# AutoPilotPanel_-_Part_2.net
KiCad netlist of a schematic drawn in EAGLE
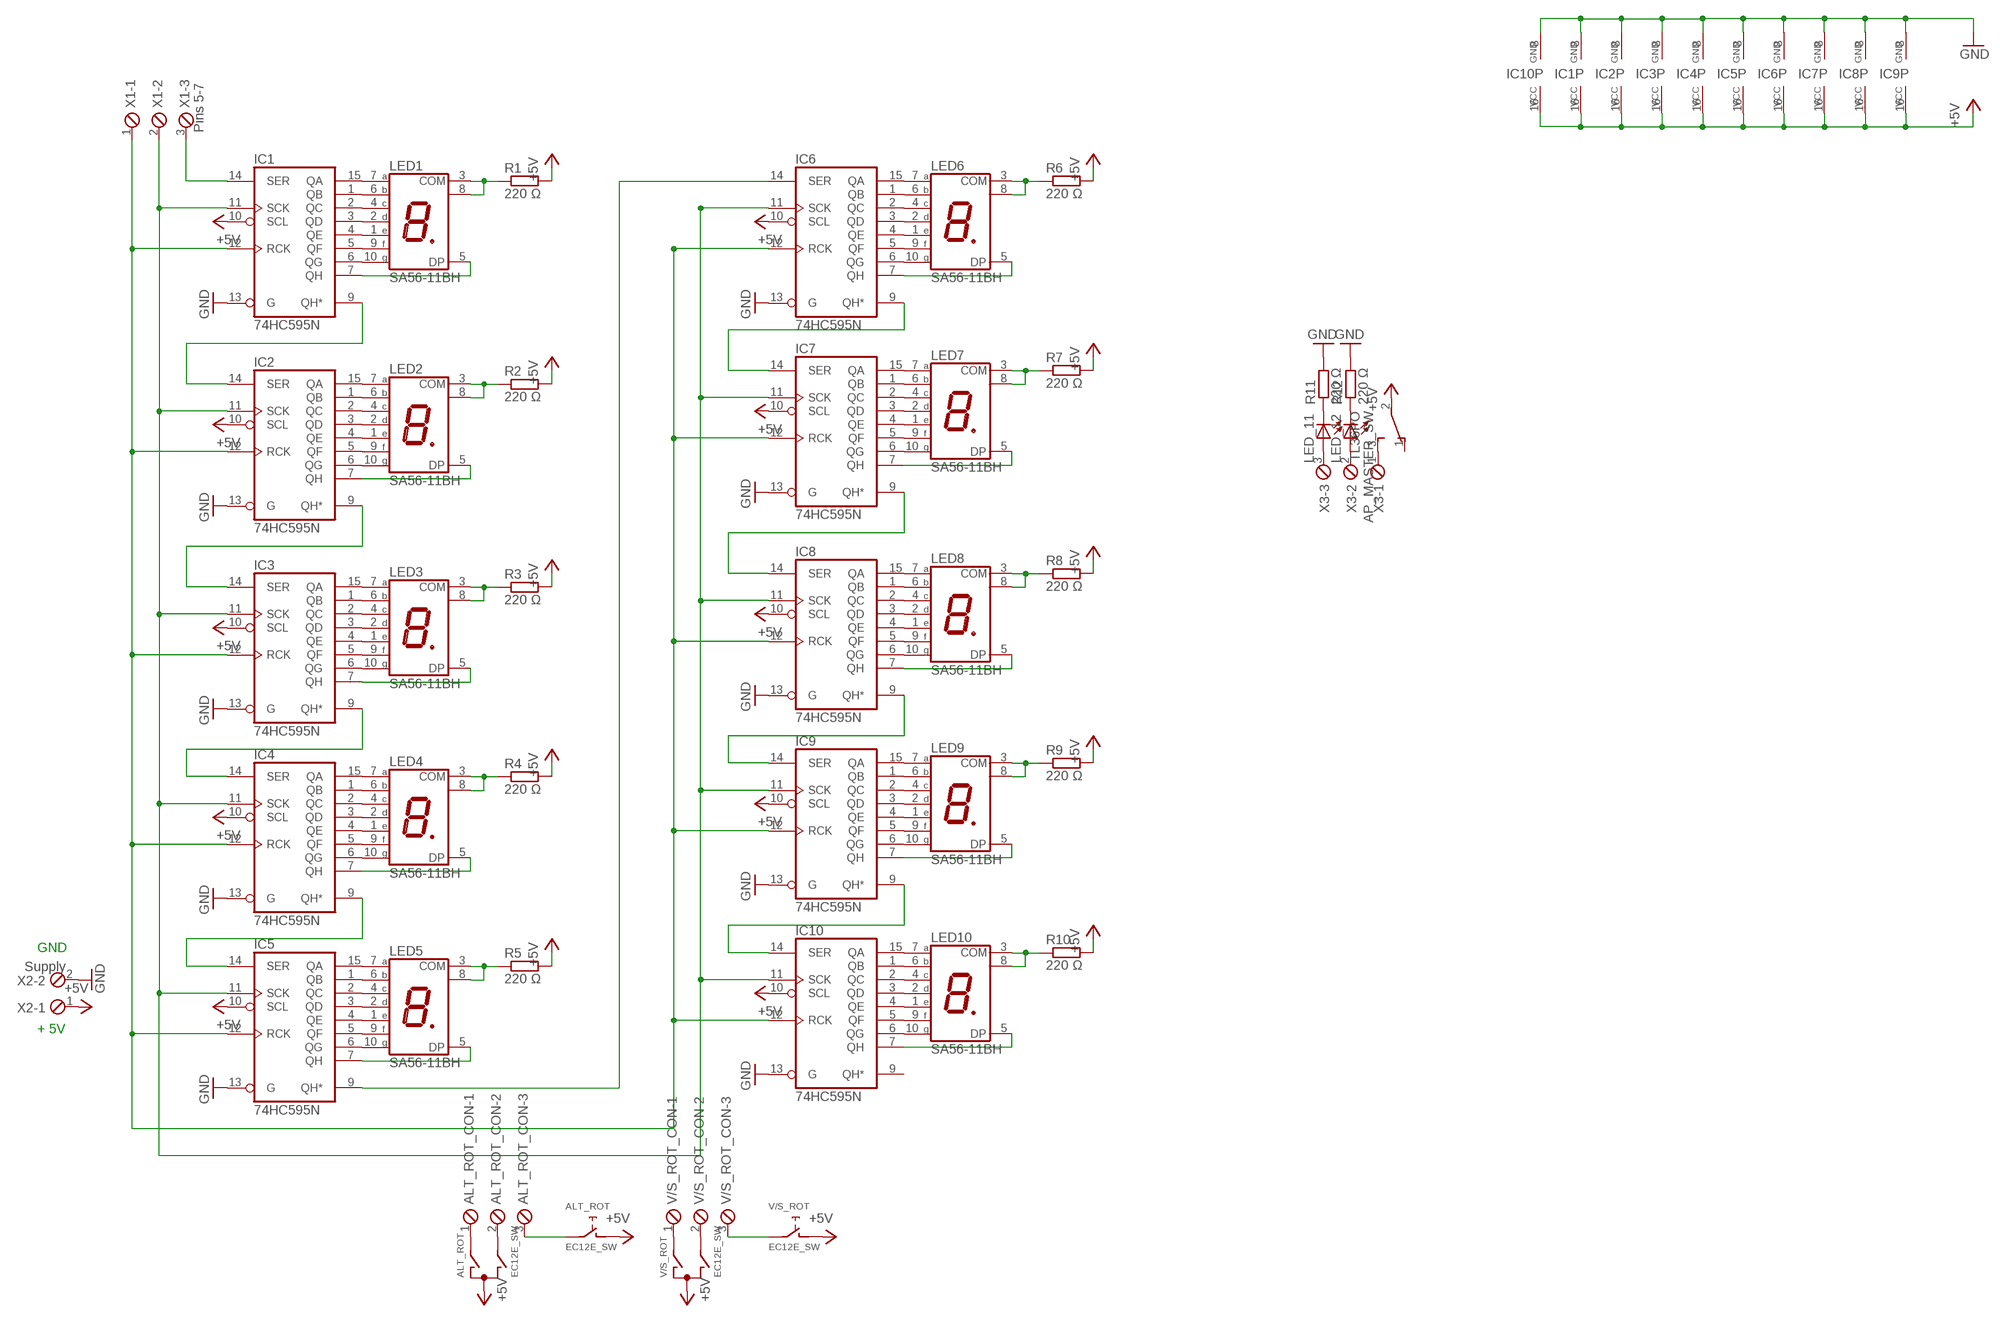
[diagram p0: schematic, sheet 1]

(export (version "E")
  (design (tool "Eeschema 10.0.6"))
  (components
    (comp (ref "ALT_ROT")
      (value "EC12E_SW")
      (footprint "eagle-import:ALPS_EC12E_SW")
      (fields (field (name "MPN") "EC12E2424407"))
      (libsource (lib "eagle-import") (part "EC12E_SW"))
    )
    (comp (ref "ALT_ROT_CON")
      (value "MPT3")
      (footprint "eagle-import:3POL254")
      (libsource (lib "eagle-import") (part "MPT3"))
    )
    (comp (ref "AP_MASTER_SW")
      (value "TL36PO")
      (footprint "eagle-import:TL3XPO")
      (libsource (lib "eagle-import") (part "TL36PO"))
    )
    (comp (ref "IC1")
      (value "74HC595N")
      (footprint "eagle-import:DIL16")
      (libsource (lib "eagle-import") (part "74595NHC"))
    )
    (comp (ref "IC2")
      (value "74HC595N")
      (footprint "eagle-import:DIL16")
      (libsource (lib "eagle-import") (part "74595NHC"))
    )
    (comp (ref "IC3")
      (value "74HC595N")
      (footprint "eagle-import:DIL16")
      (libsource (lib "eagle-import") (part "74595NHC"))
    )
    (comp (ref "IC4")
      (value "74HC595N")
      (footprint "eagle-import:DIL16")
      (libsource (lib "eagle-import") (part "74595NHC"))
    )
    (comp (ref "IC5")
      (value "74HC595N")
      (footprint "eagle-import:DIL16")
      (libsource (lib "eagle-import") (part "74595NHC"))
    )
    (comp (ref "IC6")
      (value "74HC595N")
      (footprint "eagle-import:DIL16")
      (libsource (lib "eagle-import") (part "74595NHC"))
    )
    (comp (ref "IC7")
      (value "74HC595N")
      (footprint "eagle-import:DIL16")
      (libsource (lib "eagle-import") (part "74595NHC"))
    )
    (comp (ref "IC8")
      (value "74HC595N")
      (footprint "eagle-import:DIL16")
      (libsource (lib "eagle-import") (part "74595NHC"))
    )
    (comp (ref "IC9")
      (value "74HC595N")
      (footprint "eagle-import:DIL16")
      (libsource (lib "eagle-import") (part "74595NHC"))
    )
    (comp (ref "IC10")
      (value "74HC595N")
      (footprint "eagle-import:DIL16")
      (libsource (lib "eagle-import") (part "74595NHC"))
    )
    (comp (ref "LED1")
      (value "SA56-11BH")
      (footprint "eagle-import:SA56-11")
      (libsource (lib "eagle-import") (part "7-SEG_SA56-11"))
    )
    (comp (ref "LED2")
      (value "SA56-11BH")
      (footprint "eagle-import:SA56-11")
      (libsource (lib "eagle-import") (part "7-SEG_SA56-11"))
    )
    (comp (ref "LED3")
      (value "SA56-11BH")
      (footprint "eagle-import:SA56-11")
      (libsource (lib "eagle-import") (part "7-SEG_SA56-11"))
    )
    (comp (ref "LED4")
      (value "SA56-11BH")
      (footprint "eagle-import:SA56-11")
      (libsource (lib "eagle-import") (part "7-SEG_SA56-11"))
    )
    (comp (ref "LED5")
      (value "SA56-11BH")
      (footprint "eagle-import:SA56-11")
      (libsource (lib "eagle-import") (part "7-SEG_SA56-11"))
    )
    (comp (ref "LED6")
      (value "SA56-11BH")
      (footprint "eagle-import:SA56-11")
      (libsource (lib "eagle-import") (part "7-SEG_SA56-11"))
    )
    (comp (ref "LED7")
      (value "SA56-11BH")
      (footprint "eagle-import:SA56-11")
      (libsource (lib "eagle-import") (part "7-SEG_SA56-11"))
    )
    (comp (ref "LED8")
      (value "SA56-11BH")
      (footprint "eagle-import:SA56-11")
      (libsource (lib "eagle-import") (part "7-SEG_SA56-11"))
    )
    (comp (ref "LED9")
      (value "SA56-11BH")
      (footprint "eagle-import:SA56-11")
      (libsource (lib "eagle-import") (part "7-SEG_SA56-11"))
    )
    (comp (ref "LED10")
      (value "SA56-11BH")
      (footprint "eagle-import:SA56-11")
      (libsource (lib "eagle-import") (part "7-SEG_SA56-11"))
    )
    (comp (ref "LED_11")
      (value "LED5MM")
      (footprint "eagle-import:LED5MM")
      (libsource (lib "eagle-import") (part "LED5MM"))
    )
    (comp (ref "LED_12")
      (value "LED5MM")
      (footprint "eagle-import:LED5MM")
      (libsource (lib "eagle-import") (part "LED5MM"))
    )
    (comp (ref "R1")
      (value "220 Ω")
      (footprint "eagle-import:0207_12")
      (libsource (lib "eagle-import") (part "R-EU_0207/12"))
    )
    (comp (ref "R2")
      (value "220 Ω")
      (footprint "eagle-import:0207_12")
      (libsource (lib "eagle-import") (part "R-EU_0207/12"))
    )
    (comp (ref "R3")
      (value "220 Ω")
      (footprint "eagle-import:0207_12")
      (libsource (lib "eagle-import") (part "R-EU_0207/12"))
    )
    (comp (ref "R4")
      (value "220 Ω")
      (footprint "eagle-import:0207_12")
      (libsource (lib "eagle-import") (part "R-EU_0207/12"))
    )
    (comp (ref "R5")
      (value "220 Ω")
      (footprint "eagle-import:0207_12")
      (libsource (lib "eagle-import") (part "R-EU_0207/12"))
    )
    (comp (ref "R6")
      (value "220 Ω")
      (footprint "eagle-import:0207_12")
      (libsource (lib "eagle-import") (part "R-EU_0207/12"))
    )
    (comp (ref "R7")
      (value "220 Ω")
      (footprint "eagle-import:0207_12")
      (libsource (lib "eagle-import") (part "R-EU_0207/12"))
    )
    (comp (ref "R8")
      (value "220 Ω")
      (footprint "eagle-import:0207_12")
      (libsource (lib "eagle-import") (part "R-EU_0207/12"))
    )
    (comp (ref "R9")
      (value "220 Ω")
      (footprint "eagle-import:0207_12")
      (libsource (lib "eagle-import") (part "R-EU_0207/12"))
    )
    (comp (ref "R10")
      (value "220 Ω")
      (footprint "eagle-import:0207_12")
      (libsource (lib "eagle-import") (part "R-EU_0207/12"))
    )
    (comp (ref "R11")
      (value "220 Ω")
      (footprint "eagle-import:0207_12")
      (libsource (lib "eagle-import") (part "R-EU_0207/12"))
    )
    (comp (ref "R12")
      (value "220 Ω")
      (footprint "eagle-import:0207_12")
      (libsource (lib "eagle-import") (part "R-EU_0207/12"))
    )
    (comp (ref "V/S_ROT")
      (value "EC12E_SW")
      (footprint "eagle-import:ALPS_EC12E_SW")
      (fields (field (name "MPN") "EC12E2424407"))
      (libsource (lib "eagle-import") (part "EC12E_SW"))
    )
    (comp (ref "V/S_ROT_CON")
      (value "MPT3")
      (footprint "eagle-import:3POL254")
      (libsource (lib "eagle-import") (part "MPT3"))
    )
    (comp (ref "X1")
      (value "Pins 5-7")
      (footprint "eagle-import:3POL254")
      (libsource (lib "eagle-import") (part "MPT3"))
    )
    (comp (ref "X2")
      (value "Supply")
      (footprint "eagle-import:2POL254")
      (libsource (lib "eagle-import") (part "MPT2"))
    )
    (comp (ref "X3")
      (value "MPT3")
      (footprint "eagle-import:3POL254")
      (libsource (lib "eagle-import") (part "MPT3"))
    )
  )
  (nets
    (net (code "1") (name "+5V") (class "Default")
      (node (ref "ALT_ROT") (pin "C") (pinfunction "C_C") (pintype "passive"))
      (node (ref "ALT_ROT") (pin "D") (pinfunction "1_D") (pintype "passive"))
      (node (ref "AP_MASTER_SW") (pin "2") (pinfunction "P_2") (pintype "passive"))
      (node (ref "IC1") (pin "10") (pinfunction "SCL_10") (pintype "input"))
      (node (ref "IC1") (pin "16") (pinfunction "VCC_16") (pintype "power_in"))
      (node (ref "IC10") (pin "10") (pinfunction "SCL_10") (pintype "input"))
      (node (ref "IC10") (pin "16") (pinfunction "VCC_16") (pintype "power_in"))
      (node (ref "IC2") (pin "10") (pinfunction "SCL_10") (pintype "input"))
      (node (ref "IC2") (pin "16") (pinfunction "VCC_16") (pintype "power_in"))
      (node (ref "IC3") (pin "10") (pinfunction "SCL_10") (pintype "input"))
      (node (ref "IC3") (pin "16") (pinfunction "VCC_16") (pintype "power_in"))
      (node (ref "IC4") (pin "10") (pinfunction "SCL_10") (pintype "input"))
      (node (ref "IC4") (pin "16") (pinfunction "VCC_16") (pintype "power_in"))
      (node (ref "IC5") (pin "10") (pinfunction "SCL_10") (pintype "input"))
      (node (ref "IC5") (pin "16") (pinfunction "VCC_16") (pintype "power_in"))
      (node (ref "IC6") (pin "10") (pinfunction "SCL_10") (pintype "input"))
      (node (ref "IC6") (pin "16") (pinfunction "VCC_16") (pintype "power_in"))
      (node (ref "IC7") (pin "10") (pinfunction "SCL_10") (pintype "input"))
      (node (ref "IC7") (pin "16") (pinfunction "VCC_16") (pintype "power_in"))
      (node (ref "IC8") (pin "10") (pinfunction "SCL_10") (pintype "input"))
      (node (ref "IC8") (pin "16") (pinfunction "VCC_16") (pintype "power_in"))
      (node (ref "IC9") (pin "10") (pinfunction "SCL_10") (pintype "input"))
      (node (ref "IC9") (pin "16") (pinfunction "VCC_16") (pintype "power_in"))
      (node (ref "R1") (pin "2") (pinfunction "2_2") (pintype "passive"))
      (node (ref "R10") (pin "2") (pinfunction "2_2") (pintype "passive"))
      (node (ref "R2") (pin "2") (pinfunction "2_2") (pintype "passive"))
      (node (ref "R3") (pin "2") (pinfunction "2_2") (pintype "passive"))
      (node (ref "R4") (pin "2") (pinfunction "2_2") (pintype "passive"))
      (node (ref "R5") (pin "2") (pinfunction "2_2") (pintype "passive"))
      (node (ref "R6") (pin "2") (pinfunction "2_2") (pintype "passive"))
      (node (ref "R7") (pin "2") (pinfunction "2_2") (pintype "passive"))
      (node (ref "R8") (pin "2") (pinfunction "2_2") (pintype "passive"))
      (node (ref "R9") (pin "2") (pinfunction "2_2") (pintype "passive"))
      (node (ref "V/S_ROT") (pin "C") (pinfunction "C_C") (pintype "passive"))
      (node (ref "V/S_ROT") (pin "D") (pinfunction "1_D") (pintype "passive"))
      (node (ref "X2") (pin "1") (pinfunction "1_1") (pintype "passive"))
    )
    (net (code "2") (name "GND") (class "Default")
      (node (ref "IC1") (pin "13") (pinfunction "G_13") (pintype "input"))
      (node (ref "IC1") (pin "8") (pinfunction "GND_8") (pintype "power_in"))
      (node (ref "IC10") (pin "13") (pinfunction "G_13") (pintype "input"))
      (node (ref "IC10") (pin "8") (pinfunction "GND_8") (pintype "power_in"))
      (node (ref "IC2") (pin "13") (pinfunction "G_13") (pintype "input"))
      (node (ref "IC2") (pin "8") (pinfunction "GND_8") (pintype "power_in"))
      (node (ref "IC3") (pin "13") (pinfunction "G_13") (pintype "input"))
      (node (ref "IC3") (pin "8") (pinfunction "GND_8") (pintype "power_in"))
      (node (ref "IC4") (pin "13") (pinfunction "G_13") (pintype "input"))
      (node (ref "IC4") (pin "8") (pinfunction "GND_8") (pintype "power_in"))
      (node (ref "IC5") (pin "13") (pinfunction "G_13") (pintype "input"))
      (node (ref "IC5") (pin "8") (pinfunction "GND_8") (pintype "power_in"))
      (node (ref "IC6") (pin "13") (pinfunction "G_13") (pintype "input"))
      (node (ref "IC6") (pin "8") (pinfunction "GND_8") (pintype "power_in"))
      (node (ref "IC7") (pin "13") (pinfunction "G_13") (pintype "input"))
      (node (ref "IC7") (pin "8") (pinfunction "GND_8") (pintype "power_in"))
      (node (ref "IC8") (pin "13") (pinfunction "G_13") (pintype "input"))
      (node (ref "IC8") (pin "8") (pinfunction "GND_8") (pintype "power_in"))
      (node (ref "IC9") (pin "13") (pinfunction "G_13") (pintype "input"))
      (node (ref "IC9") (pin "8") (pinfunction "GND_8") (pintype "power_in"))
      (node (ref "R11") (pin "2") (pinfunction "2_2") (pintype "passive"))
      (node (ref "R12") (pin "2") (pinfunction "2_2") (pintype "passive"))
      (node (ref "X2") (pin "2") (pinfunction "1_2") (pintype "passive"))
    )
    (net (code "3") (name "Net-(ALT_ROT-PadA)") (class "Default")
      (node (ref "ALT_ROT") (pin "A") (pinfunction "A_A") (pintype "passive"))
      (node (ref "ALT_ROT_CON") (pin "1") (pinfunction "1_1") (pintype "passive"))
    )
    (net (code "4") (name "Net-(ALT_ROTB-2)") (class "Default")
      (node (ref "ALT_ROT") (pin "E") (pinfunction "2_E") (pintype "passive"))
      (node (ref "ALT_ROT_CON") (pin "3") (pinfunction "1_3") (pintype "passive"))
    )
    (net (code "5") (name "Net-(ALT_ROT_CONB-1)") (class "Default")
      (node (ref "ALT_ROT") (pin "B") (pinfunction "B_B") (pintype "passive"))
      (node (ref "ALT_ROT_CON") (pin "2") (pinfunction "1_2") (pintype "passive"))
    )
    (net (code "6") (name "Net-(AP_MASTER_SW-S)") (class "Default")
      (node (ref "AP_MASTER_SW") (pin "3") (pinfunction "S_3") (pintype "passive"))
      (node (ref "X3") (pin "1") (pinfunction "1_1") (pintype "passive"))
    )
    (net (code "7") (name "Net-(IC1A-QA)") (class "Default")
      (node (ref "IC1") (pin "15") (pinfunction "QA_15") (pintype "tri_state"))
      (node (ref "LED1") (pin "7") (pinfunction "A_7") (pintype "passive"))
    )
    (net (code "8") (name "Net-(IC1A-QB)") (class "Default")
      (node (ref "IC1") (pin "1") (pinfunction "QB_1") (pintype "tri_state"))
      (node (ref "LED1") (pin "6") (pinfunction "B_6") (pintype "passive"))
    )
    (net (code "9") (name "Net-(IC1A-QC)") (class "Default")
      (node (ref "IC1") (pin "2") (pinfunction "QC_2") (pintype "tri_state"))
      (node (ref "LED1") (pin "4") (pinfunction "C_4") (pintype "passive"))
    )
    (net (code "10") (name "Net-(IC1A-QD)") (class "Default")
      (node (ref "IC1") (pin "3") (pinfunction "QD_3") (pintype "tri_state"))
      (node (ref "LED1") (pin "2") (pinfunction "D_2") (pintype "passive"))
    )
    (net (code "11") (name "Net-(IC1A-QE)") (class "Default")
      (node (ref "IC1") (pin "4") (pinfunction "QE_4") (pintype "tri_state"))
      (node (ref "LED1") (pin "1") (pinfunction "E_1") (pintype "passive"))
    )
    (net (code "12") (name "Net-(IC1A-QF)") (class "Default")
      (node (ref "IC1") (pin "5") (pinfunction "QF_5") (pintype "tri_state"))
      (node (ref "LED1") (pin "9") (pinfunction "F_9") (pintype "passive"))
    )
    (net (code "13") (name "Net-(IC1A-QG)") (class "Default")
      (node (ref "IC1") (pin "6") (pinfunction "QG_6") (pintype "tri_state"))
      (node (ref "LED1") (pin "10") (pinfunction "G_10") (pintype "passive"))
    )
    (net (code "14") (name "Net-(IC1A-QH)") (class "Default")
      (node (ref "IC1") (pin "7") (pinfunction "QH_7") (pintype "tri_state"))
      (node (ref "LED1") (pin "5") (pinfunction "DP_5") (pintype "passive"))
    )
    (net (code "15") (name "Net-(IC1A-QH*)") (class "Default")
      (node (ref "IC1") (pin "9") (pinfunction "QH*_9") (pintype "tri_state"))
      (node (ref "IC2") (pin "14") (pinfunction "SER_14") (pintype "input"))
    )
    (net (code "16") (name "Net-(IC1A-SER)") (class "Default")
      (node (ref "IC1") (pin "14") (pinfunction "SER_14") (pintype "input"))
      (node (ref "X1") (pin "3") (pinfunction "1_3") (pintype "passive"))
    )
    (net (code "17") (name "Net-(IC2A-QA)") (class "Default")
      (node (ref "IC2") (pin "15") (pinfunction "QA_15") (pintype "tri_state"))
      (node (ref "LED2") (pin "7") (pinfunction "A_7") (pintype "passive"))
    )
    (net (code "18") (name "Net-(IC2A-QB)") (class "Default")
      (node (ref "IC2") (pin "1") (pinfunction "QB_1") (pintype "tri_state"))
      (node (ref "LED2") (pin "6") (pinfunction "B_6") (pintype "passive"))
    )
    (net (code "19") (name "Net-(IC2A-QC)") (class "Default")
      (node (ref "IC2") (pin "2") (pinfunction "QC_2") (pintype "tri_state"))
      (node (ref "LED2") (pin "4") (pinfunction "C_4") (pintype "passive"))
    )
    (net (code "20") (name "Net-(IC2A-QD)") (class "Default")
      (node (ref "IC2") (pin "3") (pinfunction "QD_3") (pintype "tri_state"))
      (node (ref "LED2") (pin "2") (pinfunction "D_2") (pintype "passive"))
    )
    (net (code "21") (name "Net-(IC2A-QE)") (class "Default")
      (node (ref "IC2") (pin "4") (pinfunction "QE_4") (pintype "tri_state"))
      (node (ref "LED2") (pin "1") (pinfunction "E_1") (pintype "passive"))
    )
    (net (code "22") (name "Net-(IC2A-QF)") (class "Default")
      (node (ref "IC2") (pin "5") (pinfunction "QF_5") (pintype "tri_state"))
      (node (ref "LED2") (pin "9") (pinfunction "F_9") (pintype "passive"))
    )
    (net (code "23") (name "Net-(IC2A-QG)") (class "Default")
      (node (ref "IC2") (pin "6") (pinfunction "QG_6") (pintype "tri_state"))
      (node (ref "LED2") (pin "10") (pinfunction "G_10") (pintype "passive"))
    )
    (net (code "24") (name "Net-(IC2A-QH)") (class "Default")
      (node (ref "IC2") (pin "7") (pinfunction "QH_7") (pintype "tri_state"))
      (node (ref "LED2") (pin "5") (pinfunction "DP_5") (pintype "passive"))
    )
    (net (code "25") (name "Net-(IC2A-QH*)") (class "Default")
      (node (ref "IC2") (pin "9") (pinfunction "QH*_9") (pintype "tri_state"))
      (node (ref "IC3") (pin "14") (pinfunction "SER_14") (pintype "input"))
    )
    (net (code "26") (name "Net-(IC3A-QA)") (class "Default")
      (node (ref "IC3") (pin "15") (pinfunction "QA_15") (pintype "tri_state"))
      (node (ref "LED3") (pin "7") (pinfunction "A_7") (pintype "passive"))
    )
    (net (code "27") (name "Net-(IC3A-QB)") (class "Default")
      (node (ref "IC3") (pin "1") (pinfunction "QB_1") (pintype "tri_state"))
      (node (ref "LED3") (pin "6") (pinfunction "B_6") (pintype "passive"))
    )
    (net (code "28") (name "Net-(IC3A-QC)") (class "Default")
      (node (ref "IC3") (pin "2") (pinfunction "QC_2") (pintype "tri_state"))
      (node (ref "LED3") (pin "4") (pinfunction "C_4") (pintype "passive"))
    )
    (net (code "29") (name "Net-(IC3A-QD)") (class "Default")
      (node (ref "IC3") (pin "3") (pinfunction "QD_3") (pintype "tri_state"))
      (node (ref "LED3") (pin "2") (pinfunction "D_2") (pintype "passive"))
    )
    (net (code "30") (name "Net-(IC3A-QE)") (class "Default")
      (node (ref "IC3") (pin "4") (pinfunction "QE_4") (pintype "tri_state"))
      (node (ref "LED3") (pin "1") (pinfunction "E_1") (pintype "passive"))
    )
    (net (code "31") (name "Net-(IC3A-QF)") (class "Default")
      (node (ref "IC3") (pin "5") (pinfunction "QF_5") (pintype "tri_state"))
      (node (ref "LED3") (pin "9") (pinfunction "F_9") (pintype "passive"))
    )
    (net (code "32") (name "Net-(IC3A-QG)") (class "Default")
      (node (ref "IC3") (pin "6") (pinfunction "QG_6") (pintype "tri_state"))
      (node (ref "LED3") (pin "10") (pinfunction "G_10") (pintype "passive"))
    )
    (net (code "33") (name "Net-(IC3A-QH)") (class "Default")
      (node (ref "IC3") (pin "7") (pinfunction "QH_7") (pintype "tri_state"))
      (node (ref "LED3") (pin "5") (pinfunction "DP_5") (pintype "passive"))
    )
    (net (code "34") (name "Net-(IC3A-QH*)") (class "Default")
      (node (ref "IC3") (pin "9") (pinfunction "QH*_9") (pintype "tri_state"))
      (node (ref "IC4") (pin "14") (pinfunction "SER_14") (pintype "input"))
    )
    (net (code "35") (name "Net-(IC4A-QA)") (class "Default")
      (node (ref "IC4") (pin "15") (pinfunction "QA_15") (pintype "tri_state"))
      (node (ref "LED4") (pin "7") (pinfunction "A_7") (pintype "passive"))
    )
    (net (code "36") (name "Net-(IC4A-QB)") (class "Default")
      (node (ref "IC4") (pin "1") (pinfunction "QB_1") (pintype "tri_state"))
      (node (ref "LED4") (pin "6") (pinfunction "B_6") (pintype "passive"))
    )
    (net (code "37") (name "Net-(IC4A-QC)") (class "Default")
      (node (ref "IC4") (pin "2") (pinfunction "QC_2") (pintype "tri_state"))
      (node (ref "LED4") (pin "4") (pinfunction "C_4") (pintype "passive"))
    )
    (net (code "38") (name "Net-(IC4A-QD)") (class "Default")
      (node (ref "IC4") (pin "3") (pinfunction "QD_3") (pintype "tri_state"))
      (node (ref "LED4") (pin "2") (pinfunction "D_2") (pintype "passive"))
    )
    (net (code "39") (name "Net-(IC4A-QE)") (class "Default")
      (node (ref "IC4") (pin "4") (pinfunction "QE_4") (pintype "tri_state"))
      (node (ref "LED4") (pin "1") (pinfunction "E_1") (pintype "passive"))
    )
    (net (code "40") (name "Net-(IC4A-QF)") (class "Default")
      (node (ref "IC4") (pin "5") (pinfunction "QF_5") (pintype "tri_state"))
      (node (ref "LED4") (pin "9") (pinfunction "F_9") (pintype "passive"))
    )
    (net (code "41") (name "Net-(IC4A-QG)") (class "Default")
      (node (ref "IC4") (pin "6") (pinfunction "QG_6") (pintype "tri_state"))
      (node (ref "LED4") (pin "10") (pinfunction "G_10") (pintype "passive"))
    )
    (net (code "42") (name "Net-(IC4A-QH)") (class "Default")
      (node (ref "IC4") (pin "7") (pinfunction "QH_7") (pintype "tri_state"))
      (node (ref "LED4") (pin "5") (pinfunction "DP_5") (pintype "passive"))
    )
    (net (code "43") (name "Net-(IC4A-QH*)") (class "Default")
      (node (ref "IC4") (pin "9") (pinfunction "QH*_9") (pintype "tri_state"))
      (node (ref "IC5") (pin "14") (pinfunction "SER_14") (pintype "input"))
    )
    (net (code "44") (name "Net-(IC5A-QA)") (class "Default")
      (node (ref "IC5") (pin "15") (pinfunction "QA_15") (pintype "tri_state"))
      (node (ref "LED5") (pin "7") (pinfunction "A_7") (pintype "passive"))
    )
    (net (code "45") (name "Net-(IC5A-QB)") (class "Default")
      (node (ref "IC5") (pin "1") (pinfunction "QB_1") (pintype "tri_state"))
      (node (ref "LED5") (pin "6") (pinfunction "B_6") (pintype "passive"))
    )
    (net (code "46") (name "Net-(IC5A-QC)") (class "Default")
      (node (ref "IC5") (pin "2") (pinfunction "QC_2") (pintype "tri_state"))
      (node (ref "LED5") (pin "4") (pinfunction "C_4") (pintype "passive"))
    )
    (net (code "47") (name "Net-(IC5A-QD)") (class "Default")
      (node (ref "IC5") (pin "3") (pinfunction "QD_3") (pintype "tri_state"))
      (node (ref "LED5") (pin "2") (pinfunction "D_2") (pintype "passive"))
    )
    (net (code "48") (name "Net-(IC5A-QE)") (class "Default")
      (node (ref "IC5") (pin "4") (pinfunction "QE_4") (pintype "tri_state"))
      (node (ref "LED5") (pin "1") (pinfunction "E_1") (pintype "passive"))
    )
    (net (code "49") (name "Net-(IC5A-QF)") (class "Default")
      (node (ref "IC5") (pin "5") (pinfunction "QF_5") (pintype "tri_state"))
      (node (ref "LED5") (pin "9") (pinfunction "F_9") (pintype "passive"))
    )
    (net (code "50") (name "Net-(IC5A-QG)") (class "Default")
      (node (ref "IC5") (pin "6") (pinfunction "QG_6") (pintype "tri_state"))
      (node (ref "LED5") (pin "10") (pinfunction "G_10") (pintype "passive"))
    )
    (net (code "51") (name "Net-(IC5A-QH)") (class "Default")
      (node (ref "IC5") (pin "7") (pinfunction "QH_7") (pintype "tri_state"))
      (node (ref "LED5") (pin "5") (pinfunction "DP_5") (pintype "passive"))
    )
    (net (code "52") (name "Net-(IC5A-QH*)") (class "Default")
      (node (ref "IC5") (pin "9") (pinfunction "QH*_9") (pintype "tri_state"))
      (node (ref "IC6") (pin "14") (pinfunction "SER_14") (pintype "input"))
    )
    (net (code "53") (name "Net-(IC6A-QA)") (class "Default")
      (node (ref "IC6") (pin "15") (pinfunction "QA_15") (pintype "tri_state"))
      (node (ref "LED6") (pin "7") (pinfunction "A_7") (pintype "passive"))
    )
    (net (code "54") (name "Net-(IC6A-QB)") (class "Default")
      (node (ref "IC6") (pin "1") (pinfunction "QB_1") (pintype "tri_state"))
      (node (ref "LED6") (pin "6") (pinfunction "B_6") (pintype "passive"))
    )
    (net (code "55") (name "Net-(IC6A-QC)") (class "Default")
      (node (ref "IC6") (pin "2") (pinfunction "QC_2") (pintype "tri_state"))
      (node (ref "LED6") (pin "4") (pinfunction "C_4") (pintype "passive"))
    )
    (net (code "56") (name "Net-(IC6A-QD)") (class "Default")
      (node (ref "IC6") (pin "3") (pinfunction "QD_3") (pintype "tri_state"))
      (node (ref "LED6") (pin "2") (pinfunction "D_2") (pintype "passive"))
    )
    (net (code "57") (name "Net-(IC6A-QE)") (class "Default")
      (node (ref "IC6") (pin "4") (pinfunction "QE_4") (pintype "tri_state"))
      (node (ref "LED6") (pin "1") (pinfunction "E_1") (pintype "passive"))
    )
    (net (code "58") (name "Net-(IC6A-QF)") (class "Default")
      (node (ref "IC6") (pin "5") (pinfunction "QF_5") (pintype "tri_state"))
      (node (ref "LED6") (pin "9") (pinfunction "F_9") (pintype "passive"))
    )
    (net (code "59") (name "Net-(IC6A-QG)") (class "Default")
      (node (ref "IC6") (pin "6") (pinfunction "QG_6") (pintype "tri_state"))
      (node (ref "LED6") (pin "10") (pinfunction "G_10") (pintype "passive"))
    )
    (net (code "60") (name "Net-(IC6A-QH)") (class "Default")
      (node (ref "IC6") (pin "7") (pinfunction "QH_7") (pintype "tri_state"))
      (node (ref "LED6") (pin "5") (pinfunction "DP_5") (pintype "passive"))
    )
    (net (code "61") (name "Net-(IC6A-QH*)") (class "Default")
      (node (ref "IC6") (pin "9") (pinfunction "QH*_9") (pintype "tri_state"))
      (node (ref "IC7") (pin "14") (pinfunction "SER_14") (pintype "input"))
    )
    (net (code "62") (name "Net-(IC7A-QA)") (class "Default")
      (node (ref "IC7") (pin "15") (pinfunction "QA_15") (pintype "tri_state"))
      (node (ref "LED7") (pin "7") (pinfunction "A_7") (pintype "passive"))
    )
    (net (code "63") (name "Net-(IC7A-QB)") (class "Default")
      (node (ref "IC7") (pin "1") (pinfunction "QB_1") (pintype "tri_state"))
      (node (ref "LED7") (pin "6") (pinfunction "B_6") (pintype "passive"))
    )
    (net (code "64") (name "Net-(IC7A-QC)") (class "Default")
      (node (ref "IC7") (pin "2") (pinfunction "QC_2") (pintype "tri_state"))
      (node (ref "LED7") (pin "4") (pinfunction "C_4") (pintype "passive"))
    )
    (net (code "65") (name "Net-(IC7A-QD)") (class "Default")
      (node (ref "IC7") (pin "3") (pinfunction "QD_3") (pintype "tri_state"))
      (node (ref "LED7") (pin "2") (pinfunction "D_2") (pintype "passive"))
    )
    (net (code "66") (name "Net-(IC7A-QE)") (class "Default")
      (node (ref "IC7") (pin "4") (pinfunction "QE_4") (pintype "tri_state"))
      (node (ref "LED7") (pin "1") (pinfunction "E_1") (pintype "passive"))
    )
    (net (code "67") (name "Net-(IC7A-QF)") (class "Default")
      (node (ref "IC7") (pin "5") (pinfunction "QF_5") (pintype "tri_state"))
      (node (ref "LED7") (pin "9") (pinfunction "F_9") (pintype "passive"))
    )
    (net (code "68") (name "Net-(IC7A-QG)") (class "Default")
      (node (ref "IC7") (pin "6") (pinfunction "QG_6") (pintype "tri_state"))
      (node (ref "LED7") (pin "10") (pinfunction "G_10") (pintype "passive"))
    )
    (net (code "69") (name "Net-(IC7A-QH)") (class "Default")
      (node (ref "IC7") (pin "7") (pinfunction "QH_7") (pintype "tri_state"))
      (node (ref "LED7") (pin "5") (pinfunction "DP_5") (pintype "passive"))
    )
    (net (code "70") (name "Net-(IC7A-QH*)") (class "Default")
      (node (ref "IC7") (pin "9") (pinfunction "QH*_9") (pintype "tri_state"))
      (node (ref "IC8") (pin "14") (pinfunction "SER_14") (pintype "input"))
    )
    (net (code "71") (name "Net-(IC8A-QA)") (class "Default")
      (node (ref "IC8") (pin "15") (pinfunction "QA_15") (pintype "tri_state"))
      (node (ref "LED8") (pin "7") (pinfunction "A_7") (pintype "passive"))
    )
    (net (code "72") (name "Net-(IC8A-QB)") (class "Default")
      (node (ref "IC8") (pin "1") (pinfunction "QB_1") (pintype "tri_state"))
      (node (ref "LED8") (pin "6") (pinfunction "B_6") (pintype "passive"))
    )
    (net (code "73") (name "Net-(IC8A-QC)") (class "Default")
      (node (ref "IC8") (pin "2") (pinfunction "QC_2") (pintype "tri_state"))
      (node (ref "LED8") (pin "4") (pinfunction "C_4") (pintype "passive"))
    )
    (net (code "74") (name "Net-(IC8A-QD)") (class "Default")
      (node (ref "IC8") (pin "3") (pinfunction "QD_3") (pintype "tri_state"))
      (node (ref "LED8") (pin "2") (pinfunction "D_2") (pintype "passive"))
    )
    (net (code "75") (name "Net-(IC8A-QE)") (class "Default")
      (node (ref "IC8") (pin "4") (pinfunction "QE_4") (pintype "tri_state"))
      (node (ref "LED8") (pin "1") (pinfunction "E_1") (pintype "passive"))
    )
    (net (code "76") (name "Net-(IC8A-QF)") (class "Default")
      (node (ref "IC8") (pin "5") (pinfunction "QF_5") (pintype "tri_state"))
      (node (ref "LED8") (pin "9") (pinfunction "F_9") (pintype "passive"))
    )
    (net (code "77") (name "Net-(IC8A-QG)") (class "Default")
      (node (ref "IC8") (pin "6") (pinfunction "QG_6") (pintype "tri_state"))
      (node (ref "LED8") (pin "10") (pinfunction "G_10") (pintype "passive"))
    )
    (net (code "78") (name "Net-(IC8A-QH)") (class "Default")
      (node (ref "IC8") (pin "7") (pinfunction "QH_7") (pintype "tri_state"))
      (node (ref "LED8") (pin "5") (pinfunction "DP_5") (pintype "passive"))
    )
    (net (code "79") (name "Net-(IC8A-QH*)") (class "Default")
      (node (ref "IC8") (pin "9") (pinfunction "QH*_9") (pintype "tri_state"))
      (node (ref "IC9") (pin "14") (pinfunction "SER_14") (pintype "input"))
    )
    (net (code "80") (name "Net-(IC9A-QA)") (class "Default")
      (node (ref "IC9") (pin "15") (pinfunction "QA_15") (pintype "tri_state"))
      (node (ref "LED9") (pin "7") (pinfunction "A_7") (pintype "passive"))
    )
    (net (code "81") (name "Net-(IC9A-QB)") (class "Default")
      (node (ref "IC9") (pin "1") (pinfunction "QB_1") (pintype "tri_state"))
      (node (ref "LED9") (pin "6") (pinfunction "B_6") (pintype "passive"))
    )
    (net (code "82") (name "Net-(IC9A-QC)") (class "Default")
      (node (ref "IC9") (pin "2") (pinfunction "QC_2") (pintype "tri_state"))
      (node (ref "LED9") (pin "4") (pinfunction "C_4") (pintype "passive"))
    )
    (net (code "83") (name "Net-(IC9A-QD)") (class "Default")
      (node (ref "IC9") (pin "3") (pinfunction "QD_3") (pintype "tri_state"))
      (node (ref "LED9") (pin "2") (pinfunction "D_2") (pintype "passive"))
    )
    (net (code "84") (name "Net-(IC9A-QE)") (class "Default")
      (node (ref "IC9") (pin "4") (pinfunction "QE_4") (pintype "tri_state"))
      (node (ref "LED9") (pin "1") (pinfunction "E_1") (pintype "passive"))
    )
    (net (code "85") (name "Net-(IC9A-QF)") (class "Default")
      (node (ref "IC9") (pin "5") (pinfunction "QF_5") (pintype "tri_state"))
      (node (ref "LED9") (pin "9") (pinfunction "F_9") (pintype "passive"))
    )
    (net (code "86") (name "Net-(IC9A-QG)") (class "Default")
      (node (ref "IC9") (pin "6") (pinfunction "QG_6") (pintype "tri_state"))
      (node (ref "LED9") (pin "10") (pinfunction "G_10") (pintype "passive"))
    )
    (net (code "87") (name "Net-(IC9A-QH)") (class "Default")
      (node (ref "IC9") (pin "7") (pinfunction "QH_7") (pintype "tri_state"))
      (node (ref "LED9") (pin "5") (pinfunction "DP_5") (pintype "passive"))
    )
    (net (code "88") (name "Net-(IC10A-QA)") (class "Default")
      (node (ref "IC10") (pin "15") (pinfunction "QA_15") (pintype "tri_state"))
      (node (ref "LED10") (pin "7") (pinfunction "A_7") (pintype "passive"))
    )
    (net (code "89") (name "Net-(IC10A-QB)") (class "Default")
      (node (ref "IC10") (pin "1") (pinfunction "QB_1") (pintype "tri_state"))
      (node (ref "LED10") (pin "6") (pinfunction "B_6") (pintype "passive"))
    )
    (net (code "90") (name "Net-(IC10A-QC)") (class "Default")
      (node (ref "IC10") (pin "2") (pinfunction "QC_2") (pintype "tri_state"))
      (node (ref "LED10") (pin "4") (pinfunction "C_4") (pintype "passive"))
    )
    (net (code "91") (name "Net-(IC10A-QD)") (class "Default")
      (node (ref "IC10") (pin "3") (pinfunction "QD_3") (pintype "tri_state"))
      (node (ref "LED10") (pin "2") (pinfunction "D_2") (pintype "passive"))
    )
    (net (code "92") (name "Net-(IC10A-QE)") (class "Default")
      (node (ref "IC10") (pin "4") (pinfunction "QE_4") (pintype "tri_state"))
      (node (ref "LED10") (pin "1") (pinfunction "E_1") (pintype "passive"))
    )
    (net (code "93") (name "Net-(IC10A-QF)") (class "Default")
      (node (ref "IC10") (pin "5") (pinfunction "QF_5") (pintype "tri_state"))
      (node (ref "LED10") (pin "9") (pinfunction "F_9") (pintype "passive"))
    )
    (net (code "94") (name "Net-(IC10A-QG)") (class "Default")
      (node (ref "IC10") (pin "6") (pinfunction "QG_6") (pintype "tri_state"))
      (node (ref "LED10") (pin "10") (pinfunction "G_10") (pintype "passive"))
    )
    (net (code "95") (name "Net-(IC10A-QH)") (class "Default")
      (node (ref "IC10") (pin "7") (pinfunction "QH_7") (pintype "tri_state"))
      (node (ref "LED10") (pin "5") (pinfunction "DP_5") (pintype "passive"))
    )
    (net (code "96") (name "Net-(IC10A-RCK)") (class "Default")
      (node (ref "IC1") (pin "12") (pinfunction "RCK_12") (pintype "input"))
      (node (ref "IC10") (pin "12") (pinfunction "RCK_12") (pintype "input"))
      (node (ref "IC2") (pin "12") (pinfunction "RCK_12") (pintype "input"))
      (node (ref "IC3") (pin "12") (pinfunction "RCK_12") (pintype "input"))
      (node (ref "IC4") (pin "12") (pinfunction "RCK_12") (pintype "input"))
      (node (ref "IC5") (pin "12") (pinfunction "RCK_12") (pintype "input"))
      (node (ref "IC6") (pin "12") (pinfunction "RCK_12") (pintype "input"))
      (node (ref "IC7") (pin "12") (pinfunction "RCK_12") (pintype "input"))
      (node (ref "IC8") (pin "12") (pinfunction "RCK_12") (pintype "input"))
      (node (ref "IC9") (pin "12") (pinfunction "RCK_12") (pintype "input"))
      (node (ref "X1") (pin "1") (pinfunction "1_1") (pintype "passive"))
    )
    (net (code "97") (name "Net-(IC10A-SCK)") (class "Default")
      (node (ref "IC1") (pin "11") (pinfunction "SCK_11") (pintype "input"))
      (node (ref "IC10") (pin "11") (pinfunction "SCK_11") (pintype "input"))
      (node (ref "IC2") (pin "11") (pinfunction "SCK_11") (pintype "input"))
      (node (ref "IC3") (pin "11") (pinfunction "SCK_11") (pintype "input"))
      (node (ref "IC4") (pin "11") (pinfunction "SCK_11") (pintype "input"))
      (node (ref "IC5") (pin "11") (pinfunction "SCK_11") (pintype "input"))
      (node (ref "IC6") (pin "11") (pinfunction "SCK_11") (pintype "input"))
      (node (ref "IC7") (pin "11") (pinfunction "SCK_11") (pintype "input"))
      (node (ref "IC8") (pin "11") (pinfunction "SCK_11") (pintype "input"))
      (node (ref "IC9") (pin "11") (pinfunction "SCK_11") (pintype "input"))
      (node (ref "X1") (pin "2") (pinfunction "1_2") (pintype "passive"))
    )
    (net (code "98") (name "Net-(IC10A-SER)") (class "Default")
      (node (ref "IC10") (pin "14") (pinfunction "SER_14") (pintype "input"))
      (node (ref "IC9") (pin "9") (pinfunction "QH*_9") (pintype "tri_state"))
    )
    (net (code "99") (name "Net-(LED1-COM-Pad3)") (class "Default")
      (node (ref "LED1") (pin "3") (pinfunction "COM_3") (pintype "passive"))
      (node (ref "LED1") (pin "8") (pinfunction "COM_8") (pintype "passive"))
      (node (ref "R1") (pin "1") (pinfunction "1_1") (pintype "passive"))
    )
    (net (code "100") (name "Net-(LED2-COM-Pad3)") (class "Default")
      (node (ref "LED2") (pin "3") (pinfunction "COM_3") (pintype "passive"))
      (node (ref "LED2") (pin "8") (pinfunction "COM_8") (pintype "passive"))
      (node (ref "R2") (pin "1") (pinfunction "1_1") (pintype "passive"))
    )
    (net (code "101") (name "Net-(LED3-COM-Pad3)") (class "Default")
      (node (ref "LED3") (pin "3") (pinfunction "COM_3") (pintype "passive"))
      (node (ref "LED3") (pin "8") (pinfunction "COM_8") (pintype "passive"))
      (node (ref "R3") (pin "1") (pinfunction "1_1") (pintype "passive"))
    )
    (net (code "102") (name "Net-(LED4-COM-Pad3)") (class "Default")
      (node (ref "LED4") (pin "3") (pinfunction "COM_3") (pintype "passive"))
      (node (ref "LED4") (pin "8") (pinfunction "COM_8") (pintype "passive"))
      (node (ref "R4") (pin "1") (pinfunction "1_1") (pintype "passive"))
    )
    (net (code "103") (name "Net-(LED5-COM-Pad3)") (class "Default")
      (node (ref "LED5") (pin "3") (pinfunction "COM_3") (pintype "passive"))
      (node (ref "LED5") (pin "8") (pinfunction "COM_8") (pintype "passive"))
      (node (ref "R5") (pin "1") (pinfunction "1_1") (pintype "passive"))
    )
    (net (code "104") (name "Net-(LED6-COM-Pad3)") (class "Default")
      (node (ref "LED6") (pin "3") (pinfunction "COM_3") (pintype "passive"))
      (node (ref "LED6") (pin "8") (pinfunction "COM_8") (pintype "passive"))
      (node (ref "R6") (pin "1") (pinfunction "1_1") (pintype "passive"))
    )
    (net (code "105") (name "Net-(LED7-COM-Pad3)") (class "Default")
      (node (ref "LED7") (pin "3") (pinfunction "COM_3") (pintype "passive"))
      (node (ref "LED7") (pin "8") (pinfunction "COM_8") (pintype "passive"))
      (node (ref "R7") (pin "1") (pinfunction "1_1") (pintype "passive"))
    )
    (net (code "106") (name "Net-(LED8-COM-Pad3)") (class "Default")
      (node (ref "LED8") (pin "3") (pinfunction "COM_3") (pintype "passive"))
      (node (ref "LED8") (pin "8") (pinfunction "COM_8") (pintype "passive"))
      (node (ref "R8") (pin "1") (pinfunction "1_1") (pintype "passive"))
    )
    (net (code "107") (name "Net-(LED9-COM-Pad3)") (class "Default")
      (node (ref "LED9") (pin "3") (pinfunction "COM_3") (pintype "passive"))
      (node (ref "LED9") (pin "8") (pinfunction "COM_8") (pintype "passive"))
      (node (ref "R9") (pin "1") (pinfunction "1_1") (pintype "passive"))
    )
    (net (code "108") (name "Net-(LED10-COM-Pad3)") (class "Default")
      (node (ref "LED10") (pin "3") (pinfunction "COM_3") (pintype "passive"))
      (node (ref "LED10") (pin "8") (pinfunction "COM_8") (pintype "passive"))
      (node (ref "R10") (pin "1") (pinfunction "1_1") (pintype "passive"))
    )
    (net (code "109") (name "Net-(LED_11-C)") (class "Default")
      (node (ref "LED_11") (pin "K") (pinfunction "C_K") (pintype "passive"))
      (node (ref "R11") (pin "1") (pinfunction "1_1") (pintype "passive"))
    )
    (net (code "110") (name "Net-(LED_12-C)") (class "Default")
      (node (ref "LED_12") (pin "K") (pinfunction "C_K") (pintype "passive"))
      (node (ref "R12") (pin "1") (pinfunction "1_1") (pintype "passive"))
    )
    (net (code "111") (name "Net-(V/S_ROT-PadA)") (class "Default")
      (node (ref "V/S_ROT") (pin "A") (pinfunction "A_A") (pintype "passive"))
      (node (ref "V/S_ROT_CON") (pin "1") (pinfunction "1_1") (pintype "passive"))
    )
    (net (code "112") (name "Net-(V/S_ROTB-2)") (class "Default")
      (node (ref "V/S_ROT") (pin "E") (pinfunction "2_E") (pintype "passive"))
      (node (ref "V/S_ROT_CON") (pin "3") (pinfunction "1_3") (pintype "passive"))
    )
    (net (code "113") (name "Net-(V/S_ROT_CONB-1)") (class "Default")
      (node (ref "V/S_ROT") (pin "B") (pinfunction "B_B") (pintype "passive"))
      (node (ref "V/S_ROT_CON") (pin "2") (pinfunction "1_2") (pintype "passive"))
    )
    (net (code "114") (name "Net-(X3B-1)") (class "Default")
      (node (ref "LED_12") (pin "A") (pinfunction "A_A") (pintype "passive"))
      (node (ref "X3") (pin "2") (pinfunction "1_2") (pintype "passive"))
    )
    (net (code "115") (name "Net-(X3C-1)") (class "Default")
      (node (ref "LED_11") (pin "A") (pinfunction "A_A") (pintype "passive"))
      (node (ref "X3") (pin "3") (pinfunction "1_3") (pintype "passive"))
    )
    (net (code "116") (name "unconnected-(AP_MASTER_SW-O-Pad1)") (class "Default")
      (node (ref "AP_MASTER_SW") (pin "1") (pinfunction "O_1") (pintype "passive"))
    )
    (net (code "117") (name "unconnected-(IC10A-QH*-Pad9)") (class "Default")
      (node (ref "IC10") (pin "9") (pinfunction "QH*_9") (pintype "tri_state"))
    )
  )
)
